# Fuente.net
KiCad netlist of a schematic drawn in Altium Designer
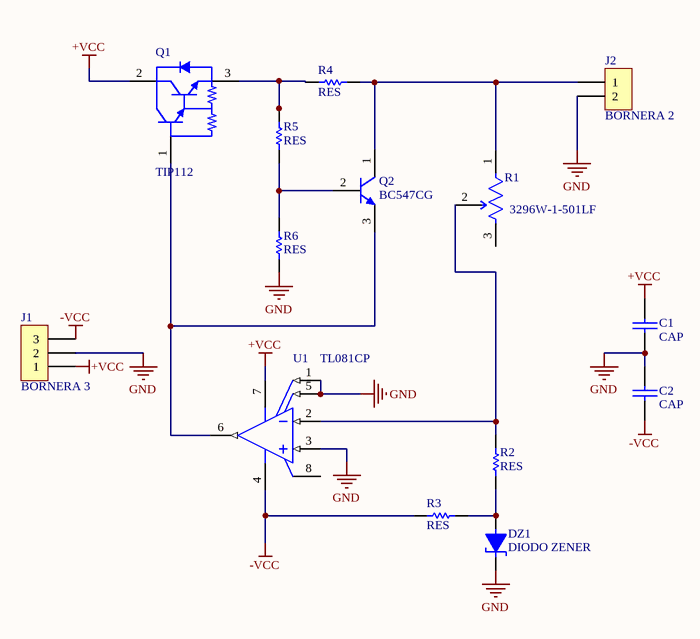
[diagram p0: Fuente.SchDoc]

(export (version "E")
  (design (tool "Eeschema 10.0.6"))
  (components
    (comp (ref "C1") (value "CAP") (footprint "CAP200") (libsource (lib "LIB PIO IX") (part "CAP")))
    (comp (ref "C2") (value "CAP") (footprint "CAP200") (libsource (lib "LIB PIO IX") (part "CAP")))
    (comp (ref "DZ1")
      (value "DIODO ZENER")
      (footprint "DO41")
      (libsource (lib "LIB PIO IX") (part "DIODO ZENER"))
    )
    (comp (ref "J1")
      (value "BORNERA 3")
      (footprint "BORNERA3")
      (libsource (lib "LIB PIO IX") (part "BORNERA 3"))
    )
    (comp (ref "J2")
      (value "BORNERA 2")
      (footprint "BORNERA2")
      (libsource (lib "LIB PIO IX") (part "BORNERA 2"))
    )
    (comp (ref "Q1")
      (value "TIP112")
      (footprint "ONSC-TO-220-3-221A-09")
      (description "Plastic Medium-Power, Complementary Silicon Transistor, 3-Pin TO-220, Tube")
      (fields (field (name "MANUFACTURER") "On Semiconductor"))
      (libsource (lib "Altium Content Vault") (part "ONSC-DT-NPN-B1C2E3-3_A"))
    )
    (comp (ref "Q2")
      (value "BC547CG")
      (footprint "ONSC-TO-92-3-29-11")
      (description "Amplifier Transistor, NPN Silicon, 3-Pin TO-92, Bulk Box")
      (fields (field (name "MANUFACTURER") "On Semiconductor") (field (name "PARTNUMBER") "BC547B"))
      (libsource (lib "Altium Content Vault") (part "ONSC-NPN-C1B2E3-3"))
    )
    (comp (ref "R1")
      (value "3296W-1-501LF")
      (footprint "FP-3296W-MFG")
      (description "TRIMMER 500 OHM 0.5W PC PIN TOP")
      (fields (field (name "TOLERANCE") "10%"))
      (libsource (lib "Altium Content Vault") (part "2dcfd2547301a7d3209a5e99acfd772"))
    )
    (comp (ref "R2") (value "RES") (footprint "RES400") (libsource (lib "LIB PIO IX") (part "RES")))
    (comp (ref "R3") (value "RES") (footprint "RES400") (libsource (lib "LIB PIO IX") (part "RES")))
    (comp (ref "R4") (value "RES") (footprint "RES600") (libsource (lib "LIB PIO IX") (part "RES")))
    (comp (ref "R5") (value "RES") (footprint "RES400") (libsource (lib "LIB PIO IX") (part "RES")))
    (comp (ref "R6") (value "RES") (footprint "RES400") (libsource (lib "LIB PIO IX") (part "RES")))
    (comp (ref "U1")
      (value "TL081CP")
      (footprint "P0008A")
      (description "JFET-Input Operational Amplifier, 7 to 36 V, 0 to 70 degC, 8-pin DIP (P8), Pb-Free (RoHS)")
      (fields (field (name "MANUFACTURER") "Texas Instruments"))
      (libsource (lib "Altium Content Vault") (part "TI-AMP-S5-2-8"))
    )
  )
  (nets
    (net (code "1") (name "+VCC") (class "Default")
      (node (ref "C1") (pin "1") (pinfunction "1_1") (pintype "passive"))
      (node (ref "J1") (pin "1") (pinfunction "1_1") (pintype "passive"))
      (node (ref "Q1") (pin "2") (pinfunction "C_2") (pintype "passive"))
      (node (ref "U1") (pin "7") (pinfunction "VCC+_7") (pintype "power_in"))
    )
    (net (code "2") (name "-VCC") (class "Default")
      (node (ref "C2") (pin "2") (pinfunction "2_2") (pintype "passive"))
      (node (ref "J1") (pin "3") (pinfunction "3_3") (pintype "passive"))
      (node (ref "R3") (pin "1") (pinfunction "1_1") (pintype "passive"))
      (node (ref "U1") (pin "4") (pinfunction "VCC-_4") (pintype "power_in"))
    )
    (net (code "3") (name "GND") (class "Default")
      (node (ref "C1") (pin "2") (pinfunction "2_2") (pintype "passive"))
      (node (ref "C2") (pin "1") (pinfunction "1_1") (pintype "passive"))
      (node (ref "DZ1") (pin "2") (pinfunction "2_2") (pintype "passive"))
      (node (ref "J1") (pin "2") (pinfunction "2_2") (pintype "passive"))
      (node (ref "J2") (pin "2") (pinfunction "2_2") (pintype "passive"))
      (node (ref "R6") (pin "1") (pinfunction "1_1") (pintype "passive"))
      (node (ref "U1") (pin "1") (pinfunction "OFFSET_N1_1") (pintype "input"))
      (node (ref "U1") (pin "3") (pinfunction "IN+_3") (pintype "input"))
      (node (ref "U1") (pin "5") (pinfunction "OFFSET_N2_5") (pintype "input"))
    )
    (net (code "4") (name "Net-(DZ1-Pad1)") (class "Default")
      (node (ref "DZ1") (pin "1") (pinfunction "1_1") (pintype "passive"))
      (node (ref "R2") (pin "2") (pinfunction "2_2") (pintype "passive"))
      (node (ref "R3") (pin "2") (pinfunction "2_2") (pintype "passive"))
    )
    (net (code "5") (name "Net-(Q1-B)") (class "Default")
      (node (ref "Q1") (pin "1") (pinfunction "B_1") (pintype "passive"))
      (node (ref "Q2") (pin "3") (pinfunction "E_3") (pintype "passive"))
      (node (ref "U1") (pin "6") (pinfunction "OUT_6") (pintype "output"))
    )
    (net (code "6") (name "Net-(Q1-E)") (class "Default")
      (node (ref "Q1") (pin "3") (pinfunction "E_3") (pintype "passive"))
      (node (ref "R4") (pin "2") (pinfunction "2_2") (pintype "passive"))
      (node (ref "R5") (pin "2") (pinfunction "2_2") (pintype "passive"))
    )
    (net (code "7") (name "Net-(Q2-B)") (class "Default")
      (node (ref "Q2") (pin "2") (pinfunction "B_2") (pintype "passive"))
      (node (ref "R5") (pin "1") (pinfunction "1_1") (pintype "passive"))
      (node (ref "R6") (pin "2") (pinfunction "2_2") (pintype "passive"))
    )
    (net (code "8") (name "Net-(Q2-C)") (class "Default")
      (node (ref "J2") (pin "1") (pinfunction "1_1") (pintype "passive"))
      (node (ref "Q2") (pin "1") (pinfunction "C_1") (pintype "passive"))
      (node (ref "R1") (pin "1") (pinfunction "CCW_1") (pintype "passive"))
      (node (ref "R4") (pin "1") (pinfunction "1_1") (pintype "passive"))
    )
    (net (code "9") (name "Net-(R1-WIPER)") (class "Default")
      (node (ref "R1") (pin "2") (pinfunction "WIPER_2") (pintype "passive"))
      (node (ref "R2") (pin "1") (pinfunction "1_1") (pintype "passive"))
      (node (ref "U1") (pin "2") (pinfunction "IN-_2") (pintype "input"))
    )
    (net (code "10") (name "unconnected-(R1-CW-Pad3)") (class "Default")
      (node (ref "R1") (pin "3") (pinfunction "CW_3") (pintype "passive"))
    )
    (net (code "11") (name "unconnected-(U1-NC-Pad8)") (class "Default")
      (node (ref "U1") (pin "8") (pinfunction "NC_8") (pintype "passive"))
    )
  )
)
